# tractor_2v5.net
KiCad netlist of a schematic drawn in EAGLE
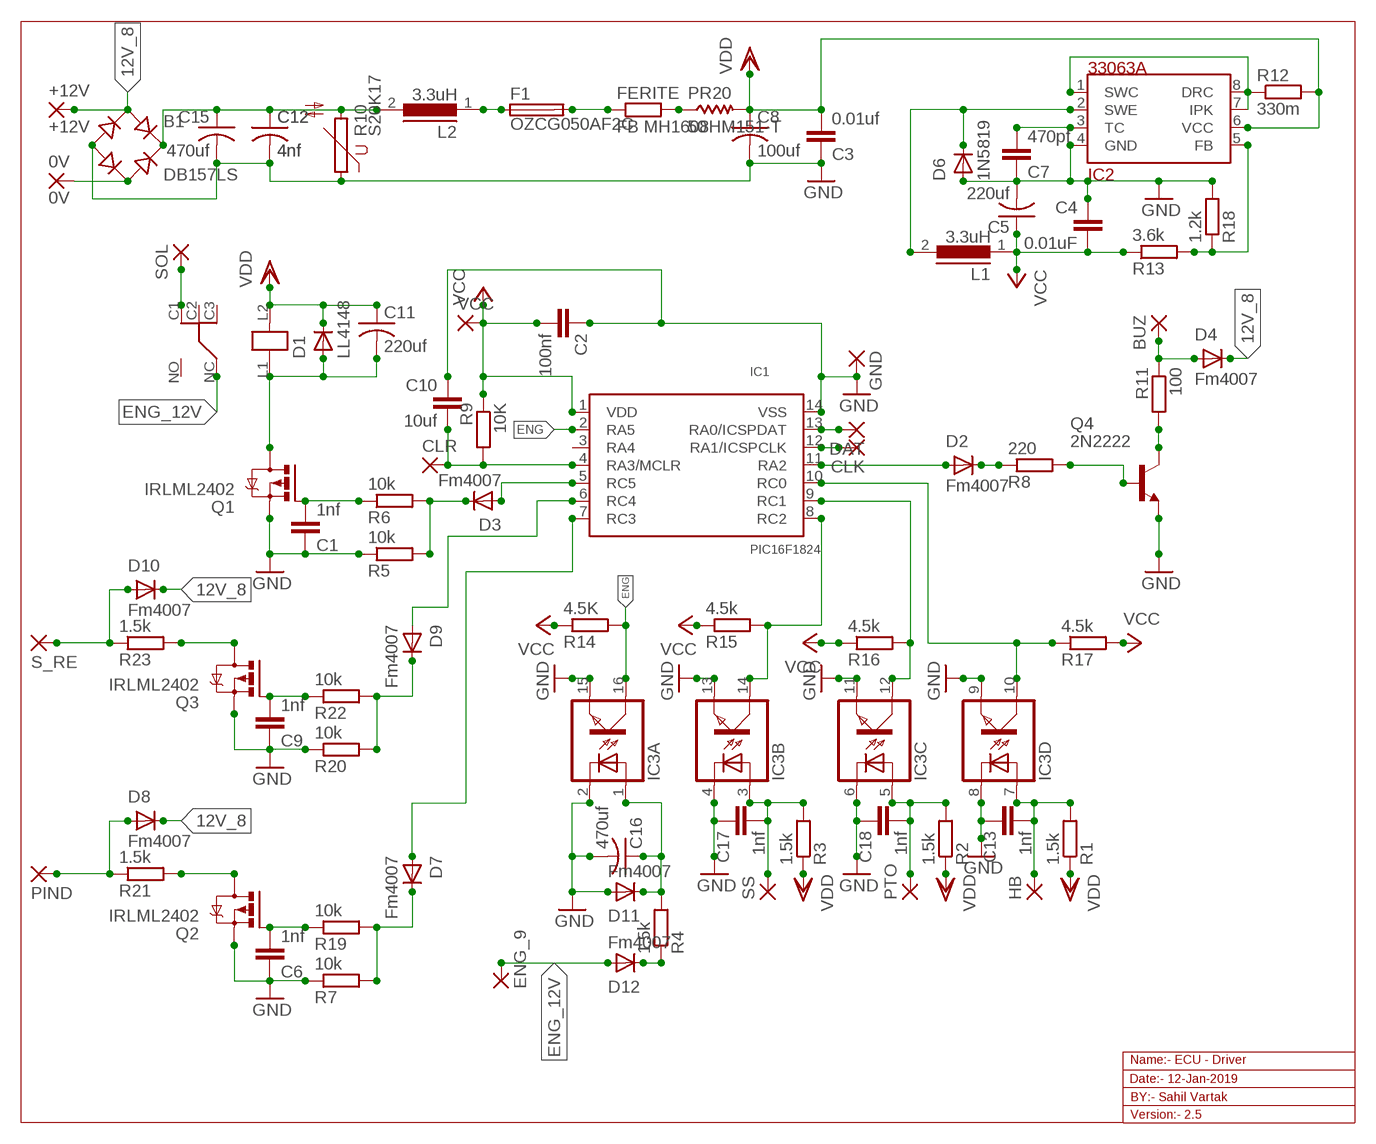
[diagram p0: schematic, sheet 1]

(export (version "E")
  (design (tool "Eeschema 10.0.6"))
  (components
    (comp (ref "+12V")
      (value "+12V")
      (footprint "eagle-import:2,54_1,1")
      (libsource (lib "eagle-import") (part "2,54/1,1"))
    )
    (comp (ref "0V")
      (value "0V")
      (footprint "eagle-import:2,54_1,1")
      (libsource (lib "eagle-import") (part "2,54/1,1"))
    )
    (comp (ref "B1")
      (value "DB157LS")
      (footprint "eagle-import:DBS")
      (libsource (lib "eagle-import") (part "DB?GS106"))
    )
    (comp (ref "BUZ")
      (value "2,54/1,1")
      (footprint "eagle-import:2,54_1,1")
      (libsource (lib "eagle-import") (part "2,54/1,1"))
    )
    (comp (ref "C1")
      (value "1nf")
      (footprint "eagle-import:C0603")
      (libsource (lib "eagle-import") (part "CC0603"))
    )
    (comp (ref "C2")
      (value "100nf")
      (footprint "eagle-import:C0603")
      (libsource (lib "eagle-import") (part "CC0603"))
    )
    (comp (ref "C3")
      (value "0.01uf")
      (footprint "eagle-import:C0603")
      (libsource (lib "eagle-import") (part "CC0603"))
    )
    (comp (ref "C4")
      (value "0.01uF")
      (footprint "eagle-import:C0603")
      (libsource (lib "eagle-import") (part "CC0603"))
    )
    (comp (ref "C5")
      (value "220uf")
      (footprint "eagle-import:C025-025X050")
      (libsource (lib "eagle-import") (part "C-US025-025X050"))
    )
    (comp (ref "C6")
      (value "1nf")
      (footprint "eagle-import:C0603")
      (libsource (lib "eagle-import") (part "CC0603"))
    )
    (comp (ref "C7")
      (value "470pf")
      (footprint "eagle-import:C0603")
      (libsource (lib "eagle-import") (part "CC0603"))
    )
    (comp (ref "C8")
      (value "100uf")
      (footprint "eagle-import:C025-025X050")
      (libsource (lib "eagle-import") (part "C-US025-025X050"))
    )
    (comp (ref "C9")
      (value "1nf")
      (footprint "eagle-import:C0603")
      (libsource (lib "eagle-import") (part "CC0603"))
    )
    (comp (ref "C10")
      (value "10uf")
      (footprint "eagle-import:C0603")
      (libsource (lib "eagle-import") (part "CC0603"))
    )
    (comp (ref "C11")
      (value "220uf")
      (footprint "eagle-import:C025-025X050")
      (libsource (lib "eagle-import") (part "C-US025-025X050"))
    )
    (comp (ref "C12")
      (value "4nf")
      (footprint "eagle-import:C050-045X075")
      (libsource (lib "eagle-import") (part "C-US050-045X075"))
    )
    (comp (ref "C13")
      (value "1nf")
      (footprint "eagle-import:C0603")
      (libsource (lib "eagle-import") (part "CC0603"))
    )
    (comp (ref "C15")
      (value "470uf")
      (footprint "eagle-import:C050-075X075")
      (libsource (lib "eagle-import") (part "resistor_C-US050-075X075"))
    )
    (comp (ref "C16")
      (value "470uf")
      (footprint "eagle-import:C050-075X075")
      (libsource (lib "eagle-import") (part "resistor_C-US050-075X075"))
    )
    (comp (ref "C17")
      (value "1nf")
      (footprint "eagle-import:C0603")
      (libsource (lib "eagle-import") (part "CC0603"))
    )
    (comp (ref "C18")
      (value "1nf")
      (footprint "eagle-import:C0603")
      (libsource (lib "eagle-import") (part "CC0603"))
    )
    (comp (ref "CLK")
      (value "1,6/0,8")
      (footprint "eagle-import:1,6_0,8")
      (libsource (lib "eagle-import") (part "1,6/0,8"))
    )
    (comp (ref "CLR")
      (value "1,6/0,8")
      (footprint "eagle-import:1,6_0,8")
      (libsource (lib "eagle-import") (part "1,6/0,8"))
    )
    (comp (ref "D1")
      (value "LL4148")
      (footprint "eagle-import:SMA-DO214AC")
      (libsource (lib "eagle-import") (part "GF1"))
    )
    (comp (ref "D2")
      (value "Fm4007")
      (footprint "eagle-import:SMA-DO214AC")
      (libsource (lib "eagle-import") (part "GF1"))
    )
    (comp (ref "D3")
      (value "Fm4007")
      (footprint "eagle-import:SMA-DO214AC")
      (libsource (lib "eagle-import") (part "GF1"))
    )
    (comp (ref "D4")
      (value "Fm4007")
      (footprint "eagle-import:SMA-DO214AC")
      (libsource (lib "eagle-import") (part "GF1"))
    )
    (comp (ref "D6")
      (value "1N5819")
      (footprint "eagle-import:SMA-DO214AC")
      (libsource (lib "eagle-import") (part "GF1"))
    )
    (comp (ref "D7")
      (value "Fm4007")
      (footprint "eagle-import:SMA-DO214AC")
      (libsource (lib "eagle-import") (part "GF1"))
    )
    (comp (ref "D8")
      (value "Fm4007")
      (footprint "eagle-import:SMA-DO214AC")
      (libsource (lib "eagle-import") (part "GF1"))
    )
    (comp (ref "D9")
      (value "Fm4007")
      (footprint "eagle-import:SMA-DO214AC")
      (libsource (lib "eagle-import") (part "GF1"))
    )
    (comp (ref "D10")
      (value "Fm4007")
      (footprint "eagle-import:SMA-DO214AC")
      (libsource (lib "eagle-import") (part "GF1"))
    )
    (comp (ref "D11")
      (value "Fm4007")
      (footprint "eagle-import:SMA-DO214AC")
      (libsource (lib "eagle-import") (part "GF1"))
    )
    (comp (ref "D12")
      (value "Fm4007")
      (footprint "eagle-import:SMA-DO214AC")
      (libsource (lib "eagle-import") (part "GF1"))
    )
    (comp (ref "DAT")
      (value "1,6/0,8")
      (footprint "eagle-import:1,6_0,8")
      (libsource (lib "eagle-import") (part "1,6/0,8"))
    )
    (comp (ref "ENG_9")
      (value "2,54/1,1")
      (footprint "eagle-import:2,54_1,1")
      (libsource (lib "eagle-import") (part "2,54/1,1"))
    )
    (comp (ref "F1")
      (value "OZCG050AF2C")
      (footprint "eagle-import:RES_FUSE")
      (libsource (lib "eagle-import") (part "RES_FUSE"))
    )
    (comp (ref "FERITE")
      (value "FB MH1608HM151-T")
      (footprint "eagle-import:R0603")
      (libsource (lib "eagle-import") (part "R-EU_R0603"))
    )
    (comp (ref "GND")
      (value "1,6/0,8")
      (footprint "eagle-import:1,6_0,8")
      (libsource (lib "eagle-import") (part "1,6/0,8"))
    )
    (comp (ref "HB")
      (value "2,54/1,1")
      (footprint "eagle-import:2,54_1,1")
      (libsource (lib "eagle-import") (part "2,54/1,1"))
    )
    (comp (ref "IC1")
      (value "PIC16F1824")
      (footprint "eagle-import:SO-14")
      (libsource (lib "eagle-import") (part "PIC16F1824"))
    )
    (comp (ref "IC2")
      (value "33063A")
      (footprint "eagle-import:D_R-PDSO-G8")
      (libsource (lib "eagle-import") (part "33063A"))
    )
    (comp (ref "IC3")
      (value "TLP283-4")
      (footprint "eagle-import:MINI-FLAT-16")
      (libsource (lib "eagle-import") (part "TLP283-4"))
    )
    (comp (ref "K2")
      (value "RL3531RL3")
      (footprint "eagle-import:RL3531")
      (libsource (lib "eagle-import") (part "RL3531RL3"))
    )
    (comp (ref "L1")
      (value "3.3uH")
      (footprint "eagle-import:82114R")
      (libsource (lib "eagle-import") (part "82114R"))
    )
    (comp (ref "L2")
      (value "3.3uH")
      (footprint "eagle-import:82114R")
      (libsource (lib "eagle-import") (part "82114R"))
    )
    (comp (ref "PIND")
      (value "2,54/1,1")
      (footprint "eagle-import:2,54_1,1")
      (libsource (lib "eagle-import") (part "2,54/1,1"))
    )
    (comp (ref "PR20")
      (value "50")
      (footprint "eagle-import:WSC2515")
      (libsource (lib "eagle-import") (part "R-US_WSC2515"))
    )
    (comp (ref "PTO")
      (value "2,54/1,1")
      (footprint "eagle-import:2,54_1,1")
      (libsource (lib "eagle-import") (part "2,54/1,1"))
    )
    (comp (ref "Q1")
      (value "IRLML2402")
      (footprint "eagle-import:MICRO3")
      (libsource (lib "eagle-import") (part "IRLML5203"))
    )
    (comp (ref "Q2")
      (value "IRLML2402")
      (footprint "eagle-import:MICRO3")
      (libsource (lib "eagle-import") (part "IRLML5203"))
    )
    (comp (ref "Q3")
      (value "IRLML2402")
      (footprint "eagle-import:MICRO3")
      (libsource (lib "eagle-import") (part "IRLML5203"))
    )
    (comp (ref "Q4")
      (value "2N2222")
      (footprint "eagle-import:TO18")
      (libsource (lib "eagle-import") (part "2N2222"))
    )
    (comp (ref "R1")
      (value "1.5k")
      (footprint "eagle-import:R0603")
      (libsource (lib "eagle-import") (part "RR0603"))
    )
    (comp (ref "R2")
      (value "1.5k")
      (footprint "eagle-import:R0603")
      (libsource (lib "eagle-import") (part "RR0603"))
    )
    (comp (ref "R3")
      (value "1.5k")
      (footprint "eagle-import:R0603")
      (libsource (lib "eagle-import") (part "RR0603"))
    )
    (comp (ref "R4")
      (value "1.5k")
      (footprint "eagle-import:R0603")
      (libsource (lib "eagle-import") (part "RR0603"))
    )
    (comp (ref "R5")
      (value "10k")
      (footprint "eagle-import:R0603")
      (libsource (lib "eagle-import") (part "RR0603"))
    )
    (comp (ref "R6")
      (value "10k")
      (footprint "eagle-import:R0603")
      (libsource (lib "eagle-import") (part "RR0603"))
    )
    (comp (ref "R7")
      (value "10k")
      (footprint "eagle-import:R0603")
      (libsource (lib "eagle-import") (part "RR0603"))
    )
    (comp (ref "R8")
      (value "220")
      (footprint "eagle-import:R0603")
      (libsource (lib "eagle-import") (part "RR0603"))
    )
    (comp (ref "R9")
      (value "10K")
      (footprint "eagle-import:R0603")
      (libsource (lib "eagle-import") (part "RR0603"))
    )
    (comp (ref "R10")
      (value "S20K17")
      (footprint "eagle-import:S14K17")
      (libsource (lib "eagle-import") (part "S14K17"))
    )
    (comp (ref "R11")
      (value "100")
      (footprint "eagle-import:R0603")
      (libsource (lib "eagle-import") (part "RR0603"))
    )
    (comp (ref "R12")
      (value "330m")
      (footprint "eagle-import:R2010")
      (libsource (lib "eagle-import") (part "RR2010"))
    )
    (comp (ref "R13")
      (value "3.6k")
      (footprint "eagle-import:R0603")
      (libsource (lib "eagle-import") (part "RR0603"))
    )
    (comp (ref "R14")
      (value "4.5K")
      (footprint "eagle-import:R0603")
      (libsource (lib "eagle-import") (part "RR0603"))
    )
    (comp (ref "R15")
      (value "4.5k")
      (footprint "eagle-import:R0603")
      (libsource (lib "eagle-import") (part "RR0603"))
    )
    (comp (ref "R16")
      (value "4.5k")
      (footprint "eagle-import:R0603")
      (libsource (lib "eagle-import") (part "RR0603"))
    )
    (comp (ref "R17")
      (value "4.5k")
      (footprint "eagle-import:R0603")
      (libsource (lib "eagle-import") (part "RR0603"))
    )
    (comp (ref "R18")
      (value "1.2k")
      (footprint "eagle-import:R0603")
      (libsource (lib "eagle-import") (part "RR0603"))
    )
    (comp (ref "R19")
      (value "10k")
      (footprint "eagle-import:R0603")
      (libsource (lib "eagle-import") (part "RR0603"))
    )
    (comp (ref "R20")
      (value "10k")
      (footprint "eagle-import:R0603")
      (libsource (lib "eagle-import") (part "RR0603"))
    )
    (comp (ref "R21")
      (value "1.5k")
      (footprint "eagle-import:R0603")
      (libsource (lib "eagle-import") (part "RR0603"))
    )
    (comp (ref "R22")
      (value "10k")
      (footprint "eagle-import:R0603")
      (libsource (lib "eagle-import") (part "RR0603"))
    )
    (comp (ref "R23")
      (value "1.5k")
      (footprint "eagle-import:R0603")
      (libsource (lib "eagle-import") (part "RR0603"))
    )
    (comp (ref "SOL")
      (value "2,54/1,1")
      (footprint "eagle-import:2,54_1,1")
      (libsource (lib "eagle-import") (part "2,54/1,1"))
    )
    (comp (ref "SS")
      (value "2,54/1,1")
      (footprint "eagle-import:2,54_1,1")
      (libsource (lib "eagle-import") (part "2,54/1,1"))
    )
    (comp (ref "S_RE")
      (value "2,54/1,1")
      (footprint "eagle-import:2,54_1,1")
      (libsource (lib "eagle-import") (part "2,54/1,1"))
    )
    (comp (ref "VCC")
      (value "1,6/0,8")
      (footprint "eagle-import:1,6_0,8")
      (libsource (lib "eagle-import") (part "1,6/0,8"))
    )
  )
  (nets
    (net (code "1") (name "12V_8") (class "Default")
      (node (ref "+12V") (pin "1") (pinfunction "P_1") (pintype "passive"))
      (node (ref "B1") (pin "AC1") (pinfunction "AC1_AC1") (pintype "passive"))
      (node (ref "D10") (pin "K") (pinfunction "C_K") (pintype "passive"))
      (node (ref "D4") (pin "K") (pinfunction "C_K") (pintype "passive"))
      (node (ref "D8") (pin "K") (pinfunction "C_K") (pintype "passive"))
    )
    (net (code "2") (name "ENG") (class "Default")
      (node (ref "IC1") (pin "2") (pinfunction "RA5_2") (pintype "bidirectional"))
      (node (ref "IC3") (pin "16") (pinfunction "COL_16") (pintype "passive"))
      (node (ref "R14") (pin "2") (pinfunction "2_2") (pintype "passive"))
    )
    (net (code "3") (name "ENG_12V") (class "Default")
      (node (ref "D12") (pin "A") (pinfunction "A_A") (pintype "passive"))
      (node (ref "ENG_9") (pin "1") (pinfunction "P_1") (pintype "passive"))
      (node (ref "K2") (pin "NC") (pinfunction "NC_NC") (pintype "output"))
    )
    (net (code "4") (name "GND") (class "Default")
      (node (ref "B1") (pin "-") (pinfunction "-_-") (pintype "passive"))
      (node (ref "C1") (pin "1") (pinfunction "1_1") (pintype "passive"))
      (node (ref "C10") (pin "1") (pinfunction "1_1") (pintype "passive"))
      (node (ref "C12") (pin "2") (pinfunction "2_2") (pintype "passive"))
      (node (ref "C13") (pin "1") (pinfunction "1_1") (pintype "passive"))
      (node (ref "C15") (pin "2") (pinfunction "2_2") (pintype "passive"))
      (node (ref "C16") (pin "2") (pinfunction "2_2") (pintype "passive"))
      (node (ref "C17") (pin "1") (pinfunction "1_1") (pintype "passive"))
      (node (ref "C18") (pin "1") (pinfunction "1_1") (pintype "passive"))
      (node (ref "C2") (pin "1") (pinfunction "1_1") (pintype "passive"))
      (node (ref "C3") (pin "1") (pinfunction "1_1") (pintype "passive"))
      (node (ref "C4") (pin "1") (pinfunction "1_1") (pintype "passive"))
      (node (ref "C5") (pin "2") (pinfunction "2_2") (pintype "passive"))
      (node (ref "C6") (pin "1") (pinfunction "1_1") (pintype "passive"))
      (node (ref "C7") (pin "1") (pinfunction "1_1") (pintype "passive"))
      (node (ref "C8") (pin "2") (pinfunction "2_2") (pintype "passive"))
      (node (ref "C9") (pin "1") (pinfunction "1_1") (pintype "passive"))
      (node (ref "D11") (pin "A") (pinfunction "A_A") (pintype "passive"))
      (node (ref "D6") (pin "A") (pinfunction "A_A") (pintype "passive"))
      (node (ref "GND") (pin "1") (pinfunction "P_1") (pintype "passive"))
      (node (ref "IC1") (pin "14") (pinfunction "VSS_14") (pintype "bidirectional"))
      (node (ref "IC2") (pin "4") (pinfunction "GND_4") (pintype "bidirectional"))
      (node (ref "IC3") (pin "11") (pinfunction "EMIT_11") (pintype "passive"))
      (node (ref "IC3") (pin "13") (pinfunction "EMIT_13") (pintype "passive"))
      (node (ref "IC3") (pin "15") (pinfunction "EMIT_15") (pintype "passive"))
      (node (ref "IC3") (pin "2") (pinfunction "C_2") (pintype "passive"))
      (node (ref "IC3") (pin "4") (pinfunction "C_4") (pintype "passive"))
      (node (ref "IC3") (pin "6") (pinfunction "C_6") (pintype "passive"))
      (node (ref "IC3") (pin "8") (pinfunction "C_8") (pintype "passive"))
      (node (ref "IC3") (pin "9") (pinfunction "EMIT_9") (pintype "passive"))
      (node (ref "Q1") (pin "2") (pinfunction "S_2") (pintype "passive"))
      (node (ref "Q2") (pin "2") (pinfunction "S_2") (pintype "passive"))
      (node (ref "Q3") (pin "2") (pinfunction "S_2") (pintype "passive"))
      (node (ref "Q4") (pin "1") (pinfunction "E_1") (pintype "passive"))
      (node (ref "R10") (pin "1") (pinfunction "1_1") (pintype "passive"))
      (node (ref "R18") (pin "2") (pinfunction "2_2") (pintype "passive"))
      (node (ref "R20") (pin "1") (pinfunction "1_1") (pintype "passive"))
      (node (ref "R5") (pin "1") (pinfunction "1_1") (pintype "passive"))
      (node (ref "R7") (pin "1") (pinfunction "1_1") (pintype "passive"))
    )
    (net (code "5") (name "Net-(0V-P)") (class "Default")
      (node (ref "0V") (pin "1") (pinfunction "P_1") (pintype "passive"))
      (node (ref "B1") (pin "AC2") (pinfunction "AC2_AC2") (pintype "passive"))
    )
    (net (code "6") (name "Net-(B1-Pad+)") (class "Default")
      (node (ref "B1") (pin "+") (pinfunction "+_+") (pintype "passive"))
      (node (ref "C12") (pin "1") (pinfunction "1_1") (pintype "passive"))
      (node (ref "C15") (pin "1") (pinfunction "1_1") (pintype "passive"))
      (node (ref "L2") (pin "2") (pinfunction "2_2") (pintype "passive"))
      (node (ref "R10") (pin "2") (pinfunction "2_2") (pintype "passive"))
    )
    (net (code "7") (name "Net-(BUZ-P)") (class "Default")
      (node (ref "BUZ") (pin "1") (pinfunction "P_1") (pintype "passive"))
      (node (ref "D4") (pin "A") (pinfunction "A_A") (pintype "passive"))
      (node (ref "R11") (pin "1") (pinfunction "1_1") (pintype "passive"))
    )
    (net (code "8") (name "Net-(CLK-P)") (class "Default")
      (node (ref "CLK") (pin "1") (pinfunction "P_1") (pintype "passive"))
      (node (ref "IC1") (pin "12") (pinfunction "RA1/ICSPCLK_12") (pintype "bidirectional"))
    )
    (net (code "9") (name "Net-(CLR-P)") (class "Default")
      (node (ref "C10") (pin "2") (pinfunction "2_2") (pintype "passive"))
      (node (ref "CLR") (pin "1") (pinfunction "P_1") (pintype "passive"))
      (node (ref "IC1") (pin "4") (pinfunction "RA3/MCLR_4") (pintype "bidirectional"))
      (node (ref "R9") (pin "2") (pinfunction "2_2") (pintype "passive"))
    )
    (net (code "10") (name "Net-(D2-C)") (class "Default")
      (node (ref "D2") (pin "K") (pinfunction "C_K") (pintype "passive"))
      (node (ref "R8") (pin "1") (pinfunction "1_1") (pintype "passive"))
    )
    (net (code "11") (name "Net-(D3-C)") (class "Default")
      (node (ref "D3") (pin "K") (pinfunction "C_K") (pintype "passive"))
      (node (ref "R5") (pin "2") (pinfunction "2_2") (pintype "passive"))
      (node (ref "R6") (pin "2") (pinfunction "2_2") (pintype "passive"))
    )
    (net (code "12") (name "Net-(D6-C)") (class "Default")
      (node (ref "D6") (pin "K") (pinfunction "C_K") (pintype "passive"))
      (node (ref "IC2") (pin "2") (pinfunction "SWE_2") (pintype "bidirectional"))
      (node (ref "L1") (pin "2") (pinfunction "2_2") (pintype "passive"))
    )
    (net (code "13") (name "Net-(D7-C)") (class "Default")
      (node (ref "D7") (pin "K") (pinfunction "C_K") (pintype "passive"))
      (node (ref "R19") (pin "2") (pinfunction "2_2") (pintype "passive"))
      (node (ref "R7") (pin "2") (pinfunction "2_2") (pintype "passive"))
    )
    (net (code "14") (name "Net-(D9-C)") (class "Default")
      (node (ref "D9") (pin "K") (pinfunction "C_K") (pintype "passive"))
      (node (ref "R20") (pin "2") (pinfunction "2_2") (pintype "passive"))
      (node (ref "R22") (pin "2") (pinfunction "2_2") (pintype "passive"))
    )
    (net (code "15") (name "Net-(D11-C)") (class "Default")
      (node (ref "C16") (pin "1") (pinfunction "1_1") (pintype "passive"))
      (node (ref "D11") (pin "K") (pinfunction "C_K") (pintype "passive"))
      (node (ref "IC3") (pin "1") (pinfunction "A_1") (pintype "passive"))
      (node (ref "R4") (pin "2") (pinfunction "2_2") (pintype "passive"))
    )
    (net (code "16") (name "Net-(D12-C)") (class "Default")
      (node (ref "D12") (pin "K") (pinfunction "C_K") (pintype "passive"))
      (node (ref "R4") (pin "1") (pinfunction "1_1") (pintype "passive"))
    )
    (net (code "17") (name "Net-(DAT-P)") (class "Default")
      (node (ref "DAT") (pin "1") (pinfunction "P_1") (pintype "passive"))
      (node (ref "IC1") (pin "13") (pinfunction "RA0/ICSPDAT_13") (pintype "bidirectional"))
    )
    (net (code "18") (name "Net-(F1-3)") (class "Default")
      (node (ref "F1") (pin "1") (pinfunction "3_1") (pintype "passive"))
      (node (ref "L2") (pin "1") (pinfunction "1_1") (pintype "passive"))
    )
    (net (code "19") (name "Net-(F1-4)") (class "Default")
      (node (ref "F1") (pin "2") (pinfunction "4_2") (pintype "passive"))
      (node (ref "FERITE") (pin "1") (pinfunction "1_1") (pintype "passive"))
    )
    (net (code "20") (name "Net-(FERITE-Pad2)") (class "Default")
      (node (ref "FERITE") (pin "2") (pinfunction "2_2") (pintype "passive"))
      (node (ref "PR20") (pin "1") (pinfunction "1_1") (pintype "passive"))
    )
    (net (code "21") (name "Net-(HB-P)") (class "Default")
      (node (ref "C13") (pin "2") (pinfunction "2_2") (pintype "passive"))
      (node (ref "HB") (pin "1") (pinfunction "P_1") (pintype "passive"))
      (node (ref "IC3") (pin "7") (pinfunction "A_7") (pintype "passive"))
      (node (ref "R1") (pin "2") (pinfunction "2_2") (pintype "passive"))
    )
    (net (code "22") (name "Net-(IC1-RA2)") (class "Default")
      (node (ref "D2") (pin "A") (pinfunction "A_A") (pintype "passive"))
      (node (ref "IC1") (pin "11") (pinfunction "RA2_11") (pintype "bidirectional"))
    )
    (net (code "23") (name "Net-(IC1-RC0)") (class "Default")
      (node (ref "IC1") (pin "10") (pinfunction "RC0_10") (pintype "bidirectional"))
      (node (ref "IC3") (pin "10") (pinfunction "COL_10") (pintype "passive"))
      (node (ref "R17") (pin "1") (pinfunction "1_1") (pintype "passive"))
    )
    (net (code "24") (name "Net-(IC1-RC1)") (class "Default")
      (node (ref "IC1") (pin "9") (pinfunction "RC1_9") (pintype "bidirectional"))
      (node (ref "IC3") (pin "12") (pinfunction "COL_12") (pintype "passive"))
      (node (ref "R16") (pin "2") (pinfunction "2_2") (pintype "passive"))
    )
    (net (code "25") (name "Net-(IC1-RC2)") (class "Default")
      (node (ref "IC1") (pin "8") (pinfunction "RC2_8") (pintype "bidirectional"))
      (node (ref "IC3") (pin "14") (pinfunction "COL_14") (pintype "passive"))
      (node (ref "R15") (pin "2") (pinfunction "2_2") (pintype "passive"))
    )
    (net (code "26") (name "Net-(IC1-RC3)") (class "Default")
      (node (ref "D7") (pin "A") (pinfunction "A_A") (pintype "passive"))
      (node (ref "IC1") (pin "7") (pinfunction "RC3_7") (pintype "bidirectional"))
    )
    (net (code "27") (name "Net-(IC1-RC4)") (class "Default")
      (node (ref "D9") (pin "A") (pinfunction "A_A") (pintype "passive"))
      (node (ref "IC1") (pin "6") (pinfunction "RC4_6") (pintype "bidirectional"))
    )
    (net (code "28") (name "Net-(IC1-RC5)") (class "Default")
      (node (ref "D3") (pin "A") (pinfunction "A_A") (pintype "passive"))
      (node (ref "IC1") (pin "5") (pinfunction "RC5_5") (pintype "bidirectional"))
    )
    (net (code "29") (name "Net-(IC2-DRC)") (class "Default")
      (node (ref "IC2") (pin "1") (pinfunction "SWC_1") (pintype "bidirectional"))
      (node (ref "IC2") (pin "7") (pinfunction "IPK_7") (pintype "bidirectional"))
      (node (ref "IC2") (pin "8") (pinfunction "DRC_8") (pintype "bidirectional"))
      (node (ref "R12") (pin "1") (pinfunction "1_1") (pintype "passive"))
    )
    (net (code "30") (name "Net-(IC2-FB)") (class "Default")
      (node (ref "IC2") (pin "5") (pinfunction "FB_5") (pintype "bidirectional"))
      (node (ref "R13") (pin "2") (pinfunction "2_2") (pintype "passive"))
      (node (ref "R18") (pin "1") (pinfunction "1_1") (pintype "passive"))
    )
    (net (code "31") (name "Net-(IC2-TC)") (class "Default")
      (node (ref "C7") (pin "2") (pinfunction "2_2") (pintype "passive"))
      (node (ref "IC2") (pin "3") (pinfunction "TC_3") (pintype "bidirectional"))
    )
    (net (code "32") (name "Net-(IC3B-A)") (class "Default")
      (node (ref "C17") (pin "2") (pinfunction "2_2") (pintype "passive"))
      (node (ref "IC3") (pin "3") (pinfunction "A_3") (pintype "passive"))
      (node (ref "R3") (pin "2") (pinfunction "2_2") (pintype "passive"))
      (node (ref "SS") (pin "1") (pinfunction "P_1") (pintype "passive"))
    )
    (net (code "33") (name "Net-(IC3C-A)") (class "Default")
      (node (ref "C18") (pin "2") (pinfunction "2_2") (pintype "passive"))
      (node (ref "IC3") (pin "5") (pinfunction "A_5") (pintype "passive"))
      (node (ref "PTO") (pin "1") (pinfunction "P_1") (pintype "passive"))
      (node (ref "R2") (pin "2") (pinfunction "2_2") (pintype "passive"))
    )
    (net (code "34") (name "Net-(PIND-P)") (class "Default")
      (node (ref "D8") (pin "A") (pinfunction "A_A") (pintype "passive"))
      (node (ref "PIND") (pin "1") (pinfunction "P_1") (pintype "passive"))
      (node (ref "R21") (pin "1") (pinfunction "1_1") (pintype "passive"))
    )
    (net (code "35") (name "Net-(Q1-D)") (class "Default")
      (node (ref "C11") (pin "2") (pinfunction "2_2") (pintype "passive"))
      (node (ref "D1") (pin "A") (pinfunction "A_A") (pintype "passive"))
      (node (ref "K2") (pin "L1") (pinfunction "L1_L1") (pintype "bidirectional"))
      (node (ref "Q1") (pin "3") (pinfunction "D_3") (pintype "passive"))
    )
    (net (code "36") (name "Net-(Q1-G)") (class "Default")
      (node (ref "C1") (pin "2") (pinfunction "2_2") (pintype "passive"))
      (node (ref "Q1") (pin "1") (pinfunction "G_1") (pintype "passive"))
      (node (ref "R6") (pin "1") (pinfunction "1_1") (pintype "passive"))
    )
    (net (code "37") (name "Net-(Q2-D)") (class "Default")
      (node (ref "Q2") (pin "3") (pinfunction "D_3") (pintype "passive"))
      (node (ref "R21") (pin "2") (pinfunction "2_2") (pintype "passive"))
    )
    (net (code "38") (name "Net-(Q2-G)") (class "Default")
      (node (ref "C6") (pin "2") (pinfunction "2_2") (pintype "passive"))
      (node (ref "Q2") (pin "1") (pinfunction "G_1") (pintype "passive"))
      (node (ref "R19") (pin "1") (pinfunction "1_1") (pintype "passive"))
    )
    (net (code "39") (name "Net-(Q3-D)") (class "Default")
      (node (ref "Q3") (pin "3") (pinfunction "D_3") (pintype "passive"))
      (node (ref "R23") (pin "2") (pinfunction "2_2") (pintype "passive"))
    )
    (net (code "40") (name "Net-(Q3-G)") (class "Default")
      (node (ref "C9") (pin "2") (pinfunction "2_2") (pintype "passive"))
      (node (ref "Q3") (pin "1") (pinfunction "G_1") (pintype "passive"))
      (node (ref "R22") (pin "1") (pinfunction "1_1") (pintype "passive"))
    )
    (net (code "41") (name "Net-(Q4-B)") (class "Default")
      (node (ref "Q4") (pin "2") (pinfunction "B_2") (pintype "passive"))
      (node (ref "R8") (pin "2") (pinfunction "2_2") (pintype "passive"))
    )
    (net (code "42") (name "Net-(Q4-C)") (class "Default")
      (node (ref "Q4") (pin "3") (pinfunction "C_3") (pintype "passive"))
      (node (ref "R11") (pin "2") (pinfunction "2_2") (pintype "passive"))
    )
    (net (code "43") (name "Net-(SOL-P)") (class "Default")
      (node (ref "K2") (pin "C1") (pinfunction "C1_C1") (pintype "bidirectional"))
      (node (ref "SOL") (pin "1") (pinfunction "P_1") (pintype "passive"))
    )
    (net (code "44") (name "Net-(S_RE-P)") (class "Default")
      (node (ref "D10") (pin "A") (pinfunction "A_A") (pintype "passive"))
      (node (ref "R23") (pin "1") (pinfunction "1_1") (pintype "passive"))
      (node (ref "S_RE") (pin "1") (pinfunction "P_1") (pintype "passive"))
    )
    (net (code "45") (name "VCC") (class "Default")
      (node (ref "C2") (pin "2") (pinfunction "2_2") (pintype "passive"))
      (node (ref "C4") (pin "2") (pinfunction "2_2") (pintype "passive"))
      (node (ref "C5") (pin "1") (pinfunction "1_1") (pintype "passive"))
      (node (ref "IC1") (pin "1") (pinfunction "VDD_1") (pintype "bidirectional"))
      (node (ref "L1") (pin "1") (pinfunction "1_1") (pintype "passive"))
      (node (ref "R13") (pin "1") (pinfunction "1_1") (pintype "passive"))
      (node (ref "R14") (pin "1") (pinfunction "1_1") (pintype "passive"))
      (node (ref "R15") (pin "1") (pinfunction "1_1") (pintype "passive"))
      (node (ref "R16") (pin "1") (pinfunction "1_1") (pintype "passive"))
      (node (ref "R17") (pin "2") (pinfunction "2_2") (pintype "passive"))
      (node (ref "R9") (pin "1") (pinfunction "1_1") (pintype "passive"))
      (node (ref "VCC") (pin "1") (pinfunction "P_1") (pintype "passive"))
    )
    (net (code "46") (name "VDD") (class "Default")
      (node (ref "C11") (pin "1") (pinfunction "1_1") (pintype "passive"))
      (node (ref "C3") (pin "2") (pinfunction "2_2") (pintype "passive"))
      (node (ref "C8") (pin "1") (pinfunction "1_1") (pintype "passive"))
      (node (ref "D1") (pin "K") (pinfunction "C_K") (pintype "passive"))
      (node (ref "IC2") (pin "6") (pinfunction "VCC_6") (pintype "bidirectional"))
      (node (ref "K2") (pin "L2") (pinfunction "L2_L2") (pintype "bidirectional"))
      (node (ref "PR20") (pin "2") (pinfunction "2_2") (pintype "passive"))
      (node (ref "R1") (pin "1") (pinfunction "1_1") (pintype "passive"))
      (node (ref "R12") (pin "2") (pinfunction "2_2") (pintype "passive"))
      (node (ref "R2") (pin "1") (pinfunction "1_1") (pintype "passive"))
      (node (ref "R3") (pin "1") (pinfunction "1_1") (pintype "passive"))
    )
    (net (code "47") (name "unconnected-(IC1-RA4-Pad3)") (class "Default")
      (node (ref "IC1") (pin "3") (pinfunction "RA4_3") (pintype "bidirectional"))
    )
    (net (code "48") (name "unconnected-(K2-PadC2)") (class "Default")
      (node (ref "K2") (pin "C2") (pinfunction "C2_C2") (pintype "bidirectional"))
    )
    (net (code "49") (name "unconnected-(K2-PadC3)") (class "Default")
      (node (ref "K2") (pin "C3") (pinfunction "C3_C3") (pintype "bidirectional"))
    )
    (net (code "50") (name "unconnected-(K2-PadNO)") (class "Default")
      (node (ref "K2") (pin "NO") (pinfunction "NO_NO") (pintype "output"))
    )
  )
)
